# T07_-BOARD_V7.net
KiCad netlist of a schematic drawn in EAGLE
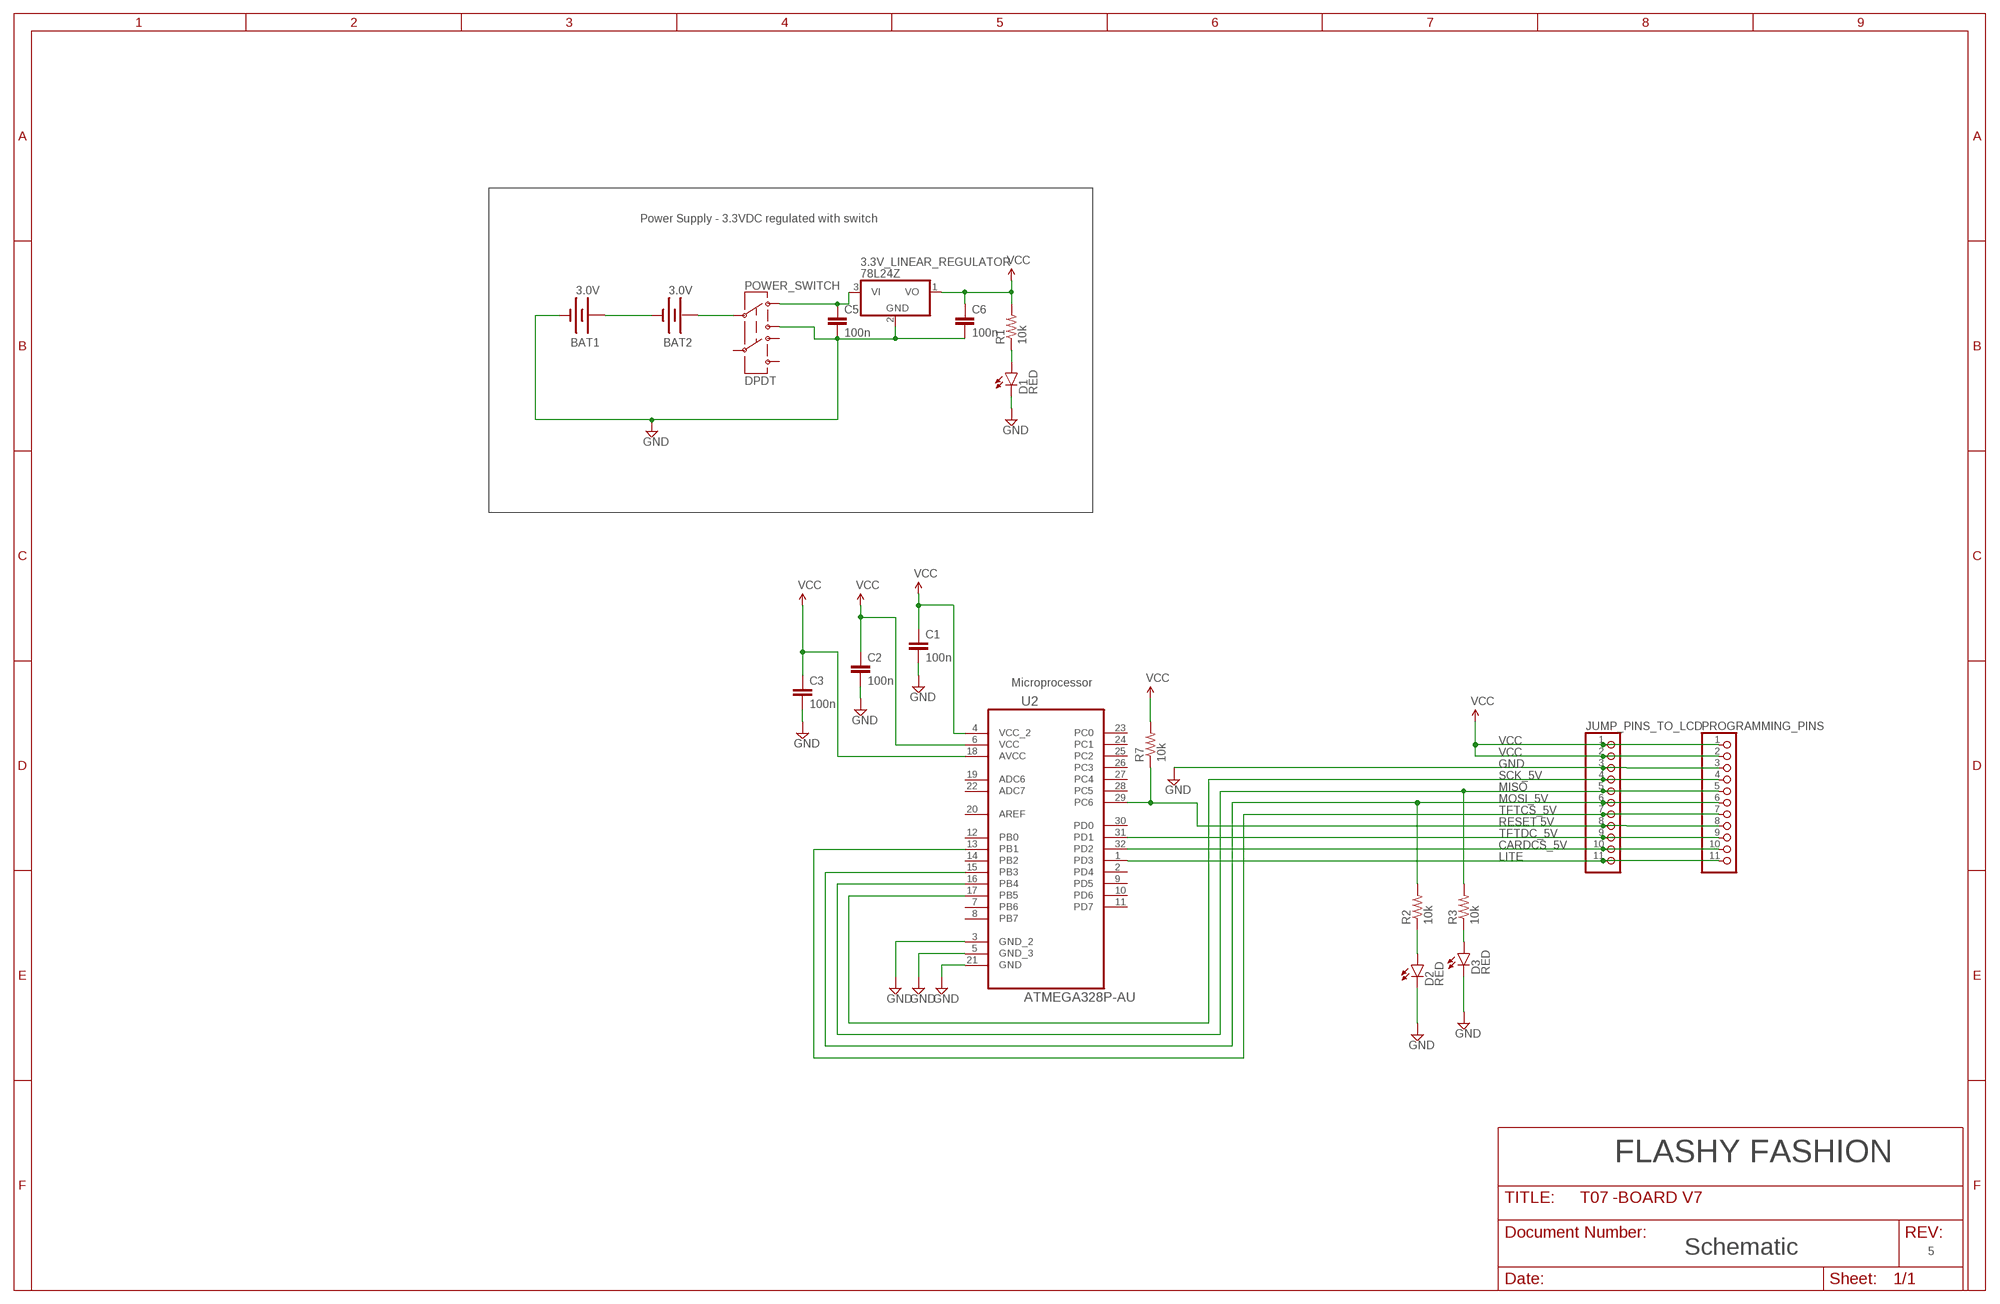
[diagram p0: schematic, sheet 1]

(export (version "E")
  (design (tool "Eeschema 10.0.6"))
  (components
    (comp (ref "3.3V_LINEAR_REGULATOR")
      (value "78L24Z")
      (footprint "eagle-import:TO92")
      (libsource (lib "eagle-import") (part "78ZL24"))
    )
    (comp (ref "BAT1")
      (value "3.0V")
      (footprint "eagle-import:BATTCON_245MM_PTH")
      (libsource (lib "eagle-import") (part "BATTERY245PTH"))
    )
    (comp (ref "BAT2")
      (value "3.0V")
      (footprint "eagle-import:BATTCON_245MM_PTH")
      (libsource (lib "eagle-import") (part "BATTERY245PTH"))
    )
    (comp (ref "C1")
      (value "100n")
      (footprint "eagle-import:1206")
      (libsource (lib "eagle-import") (part "CAP1206"))
    )
    (comp (ref "C2")
      (value "100n")
      (footprint "eagle-import:1206")
      (libsource (lib "eagle-import") (part "CAP1206"))
    )
    (comp (ref "C3")
      (value "100n")
      (footprint "eagle-import:1206")
      (libsource (lib "eagle-import") (part "CAP1206"))
    )
    (comp (ref "C5")
      (value "100n")
      (footprint "eagle-import:1206")
      (libsource (lib "eagle-import") (part "CAP1206"))
    )
    (comp (ref "C6")
      (value "100n")
      (footprint "eagle-import:1206")
      (libsource (lib "eagle-import") (part "SparkFun-Passives_CAP1206"))
    )
    (comp (ref "D1")
      (value "RED")
      (footprint "eagle-import:LED-1206")
      (libsource (lib "eagle-import") (part "LED-BLUE1206"))
    )
    (comp (ref "D2")
      (value "RED")
      (footprint "eagle-import:LED-1206")
      (libsource (lib "eagle-import") (part "LED-BLUE1206"))
    )
    (comp (ref "D3")
      (value "RED")
      (footprint "eagle-import:LED-1206")
      (libsource (lib "eagle-import") (part "LED-BLUE1206"))
    )
    (comp (ref "JUMP_PINS_TO_LCD")
      (value "HEADER-1X1176MIL")
      (footprint "eagle-import:1X11_ROUND_76")
      (libsource (lib "eagle-import") (part "HEADER-1X1176MIL"))
    )
    (comp (ref "POWER_SWITCH")
      (value "DPDT")
      (footprint "eagle-import:AYZ0202")
      (libsource (lib "eagle-import") (part "SWITCH-DPDTAYZ0202"))
    )
    (comp (ref "PROGRAMMING_PINS")
      (value "HEADER-1X1176MIL")
      (footprint "eagle-import:1X11_ROUND_76")
      (libsource (lib "eagle-import") (part "HEADER-1X1176MIL"))
    )
    (comp (ref "R1")
      (value "10k")
      (footprint "eagle-import:1206")
      (libsource (lib "eagle-import") (part "SparkFun-Resistors_RESISTOR1206"))
    )
    (comp (ref "R2")
      (value "10k")
      (footprint "eagle-import:1206")
      (libsource (lib "eagle-import") (part "SparkFun-Resistors_RESISTOR1206"))
    )
    (comp (ref "R3")
      (value "10k")
      (footprint "eagle-import:1206")
      (libsource (lib "eagle-import") (part "SparkFun-Resistors_RESISTOR1206"))
    )
    (comp (ref "R7")
      (value "10k")
      (footprint "eagle-import:1206")
      (libsource (lib "eagle-import") (part "RESISTOR1206"))
    )
    (comp (ref "U2")
      (value "ATMEGA328P-AU")
      (footprint "eagle-import:QFP80P900X900X120-32N")
      (libsource (lib "eagle-import") (part "ATMEGA328P-AU"))
    )
  )
  (nets
    (net (code "1") (name "/CARDCS_5V") (class "Default")
      (node (ref "JUMP_PINS_TO_LCD") (pin "10") (pinfunction "10_10") (pintype "passive"))
      (node (ref "PROGRAMMING_PINS") (pin "10") (pinfunction "10_10") (pintype "passive"))
      (node (ref "U2") (pin "32") (pinfunction "PD2_32") (pintype "bidirectional"))
    )
    (net (code "2") (name "/LITE") (class "Default")
      (node (ref "JUMP_PINS_TO_LCD") (pin "11") (pinfunction "11_11") (pintype "passive"))
      (node (ref "PROGRAMMING_PINS") (pin "11") (pinfunction "11_11") (pintype "passive"))
      (node (ref "U2") (pin "1") (pinfunction "PD3_1") (pintype "bidirectional"))
    )
    (net (code "3") (name "/MISO") (class "Default")
      (node (ref "JUMP_PINS_TO_LCD") (pin "5") (pinfunction "5_5") (pintype "passive"))
      (node (ref "PROGRAMMING_PINS") (pin "5") (pinfunction "5_5") (pintype "passive"))
      (node (ref "R3") (pin "2") (pinfunction "2_2") (pintype "passive"))
      (node (ref "U2") (pin "16") (pinfunction "PB4_16") (pintype "bidirectional"))
    )
    (net (code "4") (name "/MOSI_5V") (class "Default")
      (node (ref "JUMP_PINS_TO_LCD") (pin "6") (pinfunction "6_6") (pintype "passive"))
      (node (ref "PROGRAMMING_PINS") (pin "6") (pinfunction "6_6") (pintype "passive"))
      (node (ref "R2") (pin "2") (pinfunction "2_2") (pintype "passive"))
      (node (ref "U2") (pin "15") (pinfunction "PB3_15") (pintype "bidirectional"))
    )
    (net (code "5") (name "/SCK_5V") (class "Default")
      (node (ref "JUMP_PINS_TO_LCD") (pin "4") (pinfunction "4_4") (pintype "passive"))
      (node (ref "PROGRAMMING_PINS") (pin "4") (pinfunction "4_4") (pintype "passive"))
      (node (ref "U2") (pin "17") (pinfunction "PB5_17") (pintype "bidirectional"))
    )
    (net (code "6") (name "/TFTCS_5V") (class "Default")
      (node (ref "JUMP_PINS_TO_LCD") (pin "7") (pinfunction "7_7") (pintype "passive"))
      (node (ref "PROGRAMMING_PINS") (pin "7") (pinfunction "7_7") (pintype "passive"))
      (node (ref "U2") (pin "13") (pinfunction "PB1_13") (pintype "bidirectional"))
    )
    (net (code "7") (name "/TFTDC_5V") (class "Default")
      (node (ref "JUMP_PINS_TO_LCD") (pin "9") (pinfunction "9_9") (pintype "passive"))
      (node (ref "PROGRAMMING_PINS") (pin "9") (pinfunction "9_9") (pintype "passive"))
      (node (ref "U2") (pin "31") (pinfunction "PD1_31") (pintype "bidirectional"))
    )
    (net (code "8") (name "GND") (class "Default")
      (node (ref "3.3V_LINEAR_REGULATOR") (pin "2") (pinfunction "GND_2") (pintype "passive"))
      (node (ref "BAT1") (pin "2") (pinfunction "-_2") (pintype "power_in"))
      (node (ref "C1") (pin "2") (pinfunction "2_2") (pintype "passive"))
      (node (ref "C2") (pin "2") (pinfunction "2_2") (pintype "passive"))
      (node (ref "C3") (pin "2") (pinfunction "2_2") (pintype "passive"))
      (node (ref "C5") (pin "2") (pinfunction "2_2") (pintype "passive"))
      (node (ref "C6") (pin "2") (pinfunction "2_2") (pintype "passive"))
      (node (ref "D1") (pin "C") (pinfunction "C_C") (pintype "passive"))
      (node (ref "D2") (pin "C") (pinfunction "C_C") (pintype "passive"))
      (node (ref "D3") (pin "C") (pinfunction "C_C") (pintype "passive"))
      (node (ref "JUMP_PINS_TO_LCD") (pin "3") (pinfunction "3_3") (pintype "passive"))
      (node (ref "POWER_SWITCH") (pin "3") (pinfunction "3_3") (pintype "bidirectional"))
      (node (ref "PROGRAMMING_PINS") (pin "3") (pinfunction "3_3") (pintype "passive"))
      (node (ref "U2") (pin "21") (pinfunction "GND_21") (pintype "passive"))
      (node (ref "U2") (pin "3") (pinfunction "GND_2_3") (pintype "passive"))
      (node (ref "U2") (pin "5") (pinfunction "GND_3_5") (pintype "passive"))
    )
    (net (code "9") (name "Net-(3.3V_LINEAR_REGULATOR-VI)") (class "Default")
      (node (ref "3.3V_LINEAR_REGULATOR") (pin "3") (pinfunction "VI_3") (pintype "input"))
      (node (ref "C5") (pin "1") (pinfunction "1_1") (pintype "passive"))
      (node (ref "POWER_SWITCH") (pin "1") (pinfunction "1_1") (pintype "bidirectional"))
    )
    (net (code "10") (name "Net-(BAT1-+)") (class "Default")
      (node (ref "BAT1") (pin "3") (pinfunction "+_3") (pintype "power_in"))
      (node (ref "BAT2") (pin "2") (pinfunction "-_2") (pintype "power_in"))
    )
    (net (code "11") (name "Net-(BAT2-+)") (class "Default")
      (node (ref "BAT2") (pin "3") (pinfunction "+_3") (pintype "power_in"))
      (node (ref "POWER_SWITCH") (pin "2") (pinfunction "2_2") (pintype "bidirectional"))
    )
    (net (code "12") (name "Net-(D1-PadA)") (class "Default")
      (node (ref "D1") (pin "A") (pinfunction "A_A") (pintype "passive"))
      (node (ref "R1") (pin "1") (pinfunction "1_1") (pintype "passive"))
    )
    (net (code "13") (name "Net-(D2-PadA)") (class "Default")
      (node (ref "D2") (pin "A") (pinfunction "A_A") (pintype "passive"))
      (node (ref "R2") (pin "1") (pinfunction "1_1") (pintype "passive"))
    )
    (net (code "14") (name "Net-(D3-PadA)") (class "Default")
      (node (ref "D3") (pin "A") (pinfunction "A_A") (pintype "passive"))
      (node (ref "R3") (pin "1") (pinfunction "1_1") (pintype "passive"))
    )
    (net (code "15") (name "Net-(U2-PC6)") (class "Default")
      (node (ref "JUMP_PINS_TO_LCD") (pin "8") (pinfunction "8_8") (pintype "passive"))
      (node (ref "PROGRAMMING_PINS") (pin "8") (pinfunction "8_8") (pintype "passive"))
      (node (ref "R7") (pin "1") (pinfunction "1_1") (pintype "passive"))
      (node (ref "U2") (pin "29") (pinfunction "PC6_29") (pintype "bidirectional"))
    )
    (net (code "16") (name "VCC") (class "Default")
      (node (ref "3.3V_LINEAR_REGULATOR") (pin "1") (pinfunction "VO_1") (pintype "passive"))
      (node (ref "C1") (pin "1") (pinfunction "1_1") (pintype "passive"))
      (node (ref "C2") (pin "1") (pinfunction "1_1") (pintype "passive"))
      (node (ref "C3") (pin "1") (pinfunction "1_1") (pintype "passive"))
      (node (ref "C6") (pin "1") (pinfunction "1_1") (pintype "passive"))
      (node (ref "JUMP_PINS_TO_LCD") (pin "1") (pinfunction "1_1") (pintype "passive"))
      (node (ref "JUMP_PINS_TO_LCD") (pin "2") (pinfunction "2_2") (pintype "passive"))
      (node (ref "PROGRAMMING_PINS") (pin "1") (pinfunction "1_1") (pintype "passive"))
      (node (ref "PROGRAMMING_PINS") (pin "2") (pinfunction "2_2") (pintype "passive"))
      (node (ref "R1") (pin "2") (pinfunction "2_2") (pintype "passive"))
      (node (ref "R7") (pin "2") (pinfunction "2_2") (pintype "passive"))
      (node (ref "U2") (pin "18") (pinfunction "AVCC_18") (pintype "power_in"))
      (node (ref "U2") (pin "4") (pinfunction "VCC_2_4") (pintype "power_in"))
      (node (ref "U2") (pin "6") (pinfunction "VCC_6") (pintype "power_in"))
    )
    (net (code "17") (name "unconnected-(POWER_SWITCH-Pad4)") (class "Default")
      (node (ref "POWER_SWITCH") (pin "4") (pinfunction "4_4") (pintype "bidirectional"))
    )
    (net (code "18") (name "unconnected-(POWER_SWITCH-Pad5)") (class "Default")
      (node (ref "POWER_SWITCH") (pin "5") (pinfunction "5_5") (pintype "bidirectional"))
    )
    (net (code "19") (name "unconnected-(POWER_SWITCH-Pad6)") (class "Default")
      (node (ref "POWER_SWITCH") (pin "6") (pinfunction "6_6") (pintype "bidirectional"))
    )
    (net (code "20") (name "unconnected-(U2-ADC6-Pad19)") (class "Default")
      (node (ref "U2") (pin "19") (pinfunction "ADC6_19") (pintype "input"))
    )
    (net (code "21") (name "unconnected-(U2-ADC7-Pad22)") (class "Default")
      (node (ref "U2") (pin "22") (pinfunction "ADC7_22") (pintype "input"))
    )
    (net (code "22") (name "unconnected-(U2-AREF-Pad20)") (class "Default")
      (node (ref "U2") (pin "20") (pinfunction "AREF_20") (pintype "input"))
    )
    (net (code "23") (name "unconnected-(U2-PB0-Pad12)") (class "Default")
      (node (ref "U2") (pin "12") (pinfunction "PB0_12") (pintype "bidirectional"))
    )
    (net (code "24") (name "unconnected-(U2-PB2-Pad14)") (class "Default")
      (node (ref "U2") (pin "14") (pinfunction "PB2_14") (pintype "bidirectional"))
    )
    (net (code "25") (name "unconnected-(U2-PB6-Pad7)") (class "Default")
      (node (ref "U2") (pin "7") (pinfunction "PB6_7") (pintype "bidirectional"))
    )
    (net (code "26") (name "unconnected-(U2-PB7-Pad8)") (class "Default")
      (node (ref "U2") (pin "8") (pinfunction "PB7_8") (pintype "bidirectional"))
    )
    (net (code "27") (name "unconnected-(U2-PC0-Pad23)") (class "Default")
      (node (ref "U2") (pin "23") (pinfunction "PC0_23") (pintype "bidirectional"))
    )
    (net (code "28") (name "unconnected-(U2-PC1-Pad24)") (class "Default")
      (node (ref "U2") (pin "24") (pinfunction "PC1_24") (pintype "bidirectional"))
    )
    (net (code "29") (name "unconnected-(U2-PC2-Pad25)") (class "Default")
      (node (ref "U2") (pin "25") (pinfunction "PC2_25") (pintype "bidirectional"))
    )
    (net (code "30") (name "unconnected-(U2-PC3-Pad26)") (class "Default")
      (node (ref "U2") (pin "26") (pinfunction "PC3_26") (pintype "bidirectional"))
    )
    (net (code "31") (name "unconnected-(U2-PC4-Pad27)") (class "Default")
      (node (ref "U2") (pin "27") (pinfunction "PC4_27") (pintype "bidirectional"))
    )
    (net (code "32") (name "unconnected-(U2-PC5-Pad28)") (class "Default")
      (node (ref "U2") (pin "28") (pinfunction "PC5_28") (pintype "bidirectional"))
    )
    (net (code "33") (name "unconnected-(U2-PD0-Pad30)") (class "Default")
      (node (ref "U2") (pin "30") (pinfunction "PD0_30") (pintype "bidirectional"))
    )
    (net (code "34") (name "unconnected-(U2-PD4-Pad2)") (class "Default")
      (node (ref "U2") (pin "2") (pinfunction "PD4_2") (pintype "bidirectional"))
    )
    (net (code "35") (name "unconnected-(U2-PD5-Pad9)") (class "Default")
      (node (ref "U2") (pin "9") (pinfunction "PD5_9") (pintype "bidirectional"))
    )
    (net (code "36") (name "unconnected-(U2-PD6-Pad10)") (class "Default")
      (node (ref "U2") (pin "10") (pinfunction "PD6_10") (pintype "bidirectional"))
    )
    (net (code "37") (name "unconnected-(U2-PD7-Pad11)") (class "Default")
      (node (ref "U2") (pin "11") (pinfunction "PD7_11") (pintype "bidirectional"))
    )
  )
)
